# base_power_assy_PCB.net
KiCad netlist of a schematic drawn in Altium Designer
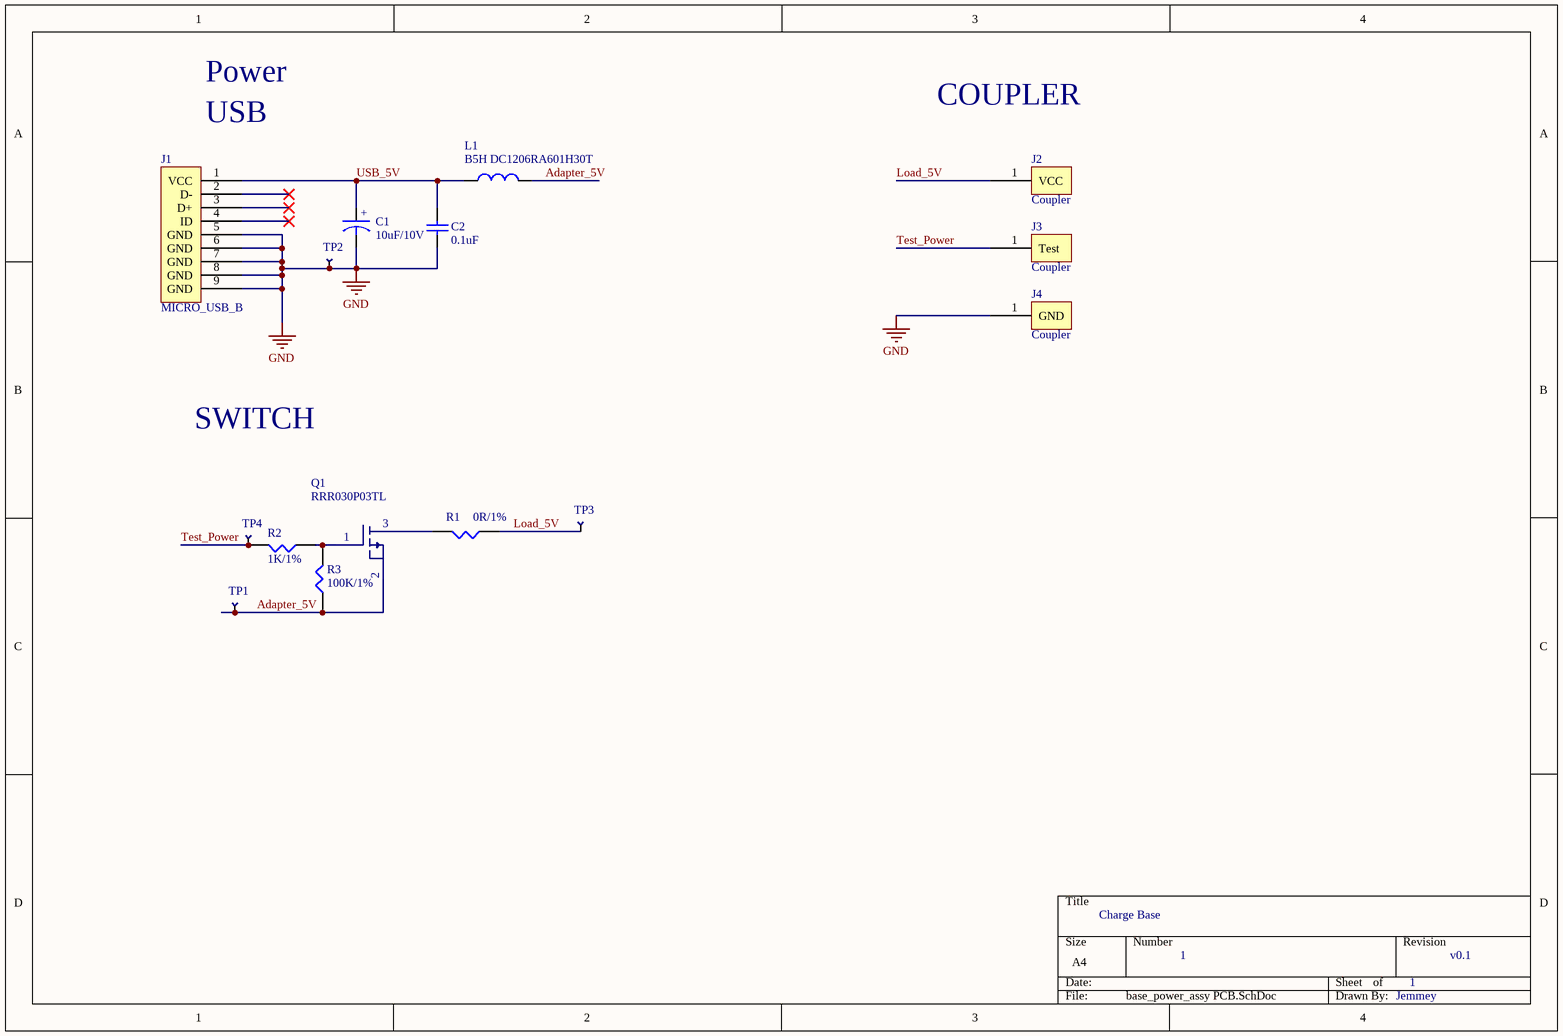
[diagram p0: base_power_assy PCB.SchDoc]

(export (version "E")
  (design (tool "Eeschema 10.0.6"))
  (components
    (comp (ref "C1") (value "10uF/10V") (footprint "3216") (libsource (lib "MoJi LIB") (part "Capacitor")))
    (comp (ref "C2")
      (value "0.1uF")
      (footprint "0402C")
      (fields (field (name "PUBLISHER") "Altium Limited"))
      (libsource (lib "器件库") (part "Cap"))
    )
    (comp (ref "J1")
      (value "MICRO_USB_B")
      (footprint "Micro-USB-乐沪")
      (description "厂家：AVX，型号：20-6751-005-001-007")
      (libsource (lib "base_power_assy PCB") (part "USB_B"))
    )
    (comp (ref "J2")
      (value "Coupler")
      (footprint "Coupler - 1")
      (description "厂家：待定；型号：待定")
      (libsource (lib "") (part "Coupler_1"))
    )
    (comp (ref "J3")
      (value "Coupler")
      (footprint "Coupler - 1")
      (description "厂家：待定；型号：待定")
      (libsource (lib "") (part "Coupler_2"))
    )
    (comp (ref "J4")
      (value "Coupler")
      (footprint "Coupler - 1")
      (description "厂家：待定；型号：待定")
      (libsource (lib "Power Connect Board") (part "Coupler"))
    )
    (comp (ref "L1")
      (value "B5H DC1206RA601H30T")
      (footprint "1206")
      (description "厂家：宇磁，型号：B5H DC1206RA601H30T")
      (libsource (lib "Amber") (part "CHOKE"))
    )
    (comp (ref "Q1")
      (value "RRR030P03TL")
      (footprint "TSMT3")
      (description "厂家：ROHM，型号：RRR030P03TL")
      (libsource (lib "*") (part "PMOS"))
    )
    (comp (ref "R1")
      (value "0R/1%")
      (footprint "0805")
      (description "厂家：Yageo，型号：RC0402FR-070RL")
      (libsource (lib "*") (part "RES1"))
    )
    (comp (ref "R2")
      (value "1K/1%")
      (footprint "0402R")
      (description "厂家：Yageo，型号：RC0402FR-071KL")
      (libsource (lib "Schlib1") (part "RES"))
    )
    (comp (ref "R3")
      (value "100K/1%")
      (footprint "0402R")
      (description "厂家：Yageo，型号：RC0402FR-07100KL")
      (libsource (lib "Schlib1") (part "RES"))
    )
    (comp (ref "TP1")
      (value "TEST")
      (footprint "Test Pad")
      (description "Test Point")
      (libsource (lib "Amber") (part "TEST"))
    )
    (comp (ref "TP2")
      (value "TEST")
      (footprint "Test Pad")
      (description "Test Point")
      (libsource (lib "Amber") (part "TEST"))
    )
    (comp (ref "TP3")
      (value "TEST")
      (footprint "Test Pad")
      (description "Test Point")
      (libsource (lib "Amber") (part "TEST"))
    )
    (comp (ref "TP4")
      (value "TEST")
      (footprint "Test Pad")
      (description "Test Point")
      (libsource (lib "Amber") (part "TEST"))
    )
  )
  (nets
    (net (code "1") (name "/Adapter_5V") (class "Default")
      (node (ref "L1") (pin "2") (pinfunction "2_2") (pintype "passive"))
      (node (ref "Q1") (pin "2") (pinfunction "S_2") (pintype "passive"))
      (node (ref "R3") (pin "1") (pinfunction "1_1") (pintype "passive"))
      (node (ref "TP1") (pin "1") (pinfunction "1_1") (pintype "passive"))
    )
    (net (code "2") (name "/Load_5V") (class "Default")
      (node (ref "J2") (pin "1") (pinfunction "VCC_1") (pintype "passive"))
      (node (ref "R1") (pin "1") (pinfunction "1_1") (pintype "passive"))
      (node (ref "TP3") (pin "1") (pinfunction "1_1") (pintype "passive"))
    )
    (net (code "3") (name "/Test_Power") (class "Default")
      (node (ref "J3") (pin "1") (pinfunction "Test_1") (pintype "passive"))
      (node (ref "R2") (pin "2") (pinfunction "2_2") (pintype "passive"))
      (node (ref "TP4") (pin "1") (pinfunction "1_1") (pintype "passive"))
    )
    (net (code "4") (name "/USB_5V") (class "Default")
      (node (ref "C1") (pin "1") (pinfunction "1_1") (pintype "passive"))
      (node (ref "C2") (pin "2") (pinfunction "2_2") (pintype "passive"))
      (node (ref "J1") (pin "1") (pinfunction "VCC_1") (pintype "passive"))
      (node (ref "L1") (pin "1") (pinfunction "1_1") (pintype "passive"))
    )
    (net (code "5") (name "GND") (class "Default")
      (node (ref "C1") (pin "2") (pinfunction "2_2") (pintype "passive"))
      (node (ref "C2") (pin "1") (pinfunction "1_1") (pintype "passive"))
      (node (ref "J1") (pin "5") (pinfunction "GND_5") (pintype "passive"))
      (node (ref "J1") (pin "6") (pinfunction "GND_6") (pintype "passive"))
      (node (ref "J1") (pin "7") (pinfunction "GND_7") (pintype "passive"))
      (node (ref "J1") (pin "8") (pinfunction "GND_8") (pintype "passive"))
      (node (ref "J1") (pin "9") (pinfunction "GND_9") (pintype "passive"))
      (node (ref "J4") (pin "1") (pinfunction "GND_1") (pintype "passive"))
      (node (ref "TP2") (pin "1") (pinfunction "1_1") (pintype "passive"))
    )
    (net (code "6") (name "Net-(Q1-D)") (class "Default")
      (node (ref "Q1") (pin "3") (pinfunction "D_3") (pintype "passive"))
      (node (ref "R1") (pin "2") (pinfunction "2_2") (pintype "passive"))
    )
    (net (code "7") (name "Net-(Q1-G)") (class "Default")
      (node (ref "Q1") (pin "1") (pinfunction "G_1") (pintype "passive"))
      (node (ref "R2") (pin "1") (pinfunction "1_1") (pintype "passive"))
      (node (ref "R3") (pin "2") (pinfunction "2_2") (pintype "passive"))
    )
    (net (code "8") (name "unconnected-(J1-D+-Pad3)") (class "Default")
      (node (ref "J1") (pin "3") (pinfunction "D+_3") (pintype "passive+no_connect"))
    )
    (net (code "9") (name "unconnected-(J1-D--Pad2)") (class "Default")
      (node (ref "J1") (pin "2") (pinfunction "D-_2") (pintype "passive+no_connect"))
    )
    (net (code "10") (name "unconnected-(J1-ID-Pad4)") (class "Default")
      (node (ref "J1") (pin "4") (pinfunction "ID_4") (pintype "passive+no_connect"))
    )
  )
)
